# 5_Way_Flex_Switch.net
KiCad netlist of a schematic drawn in EAGLE
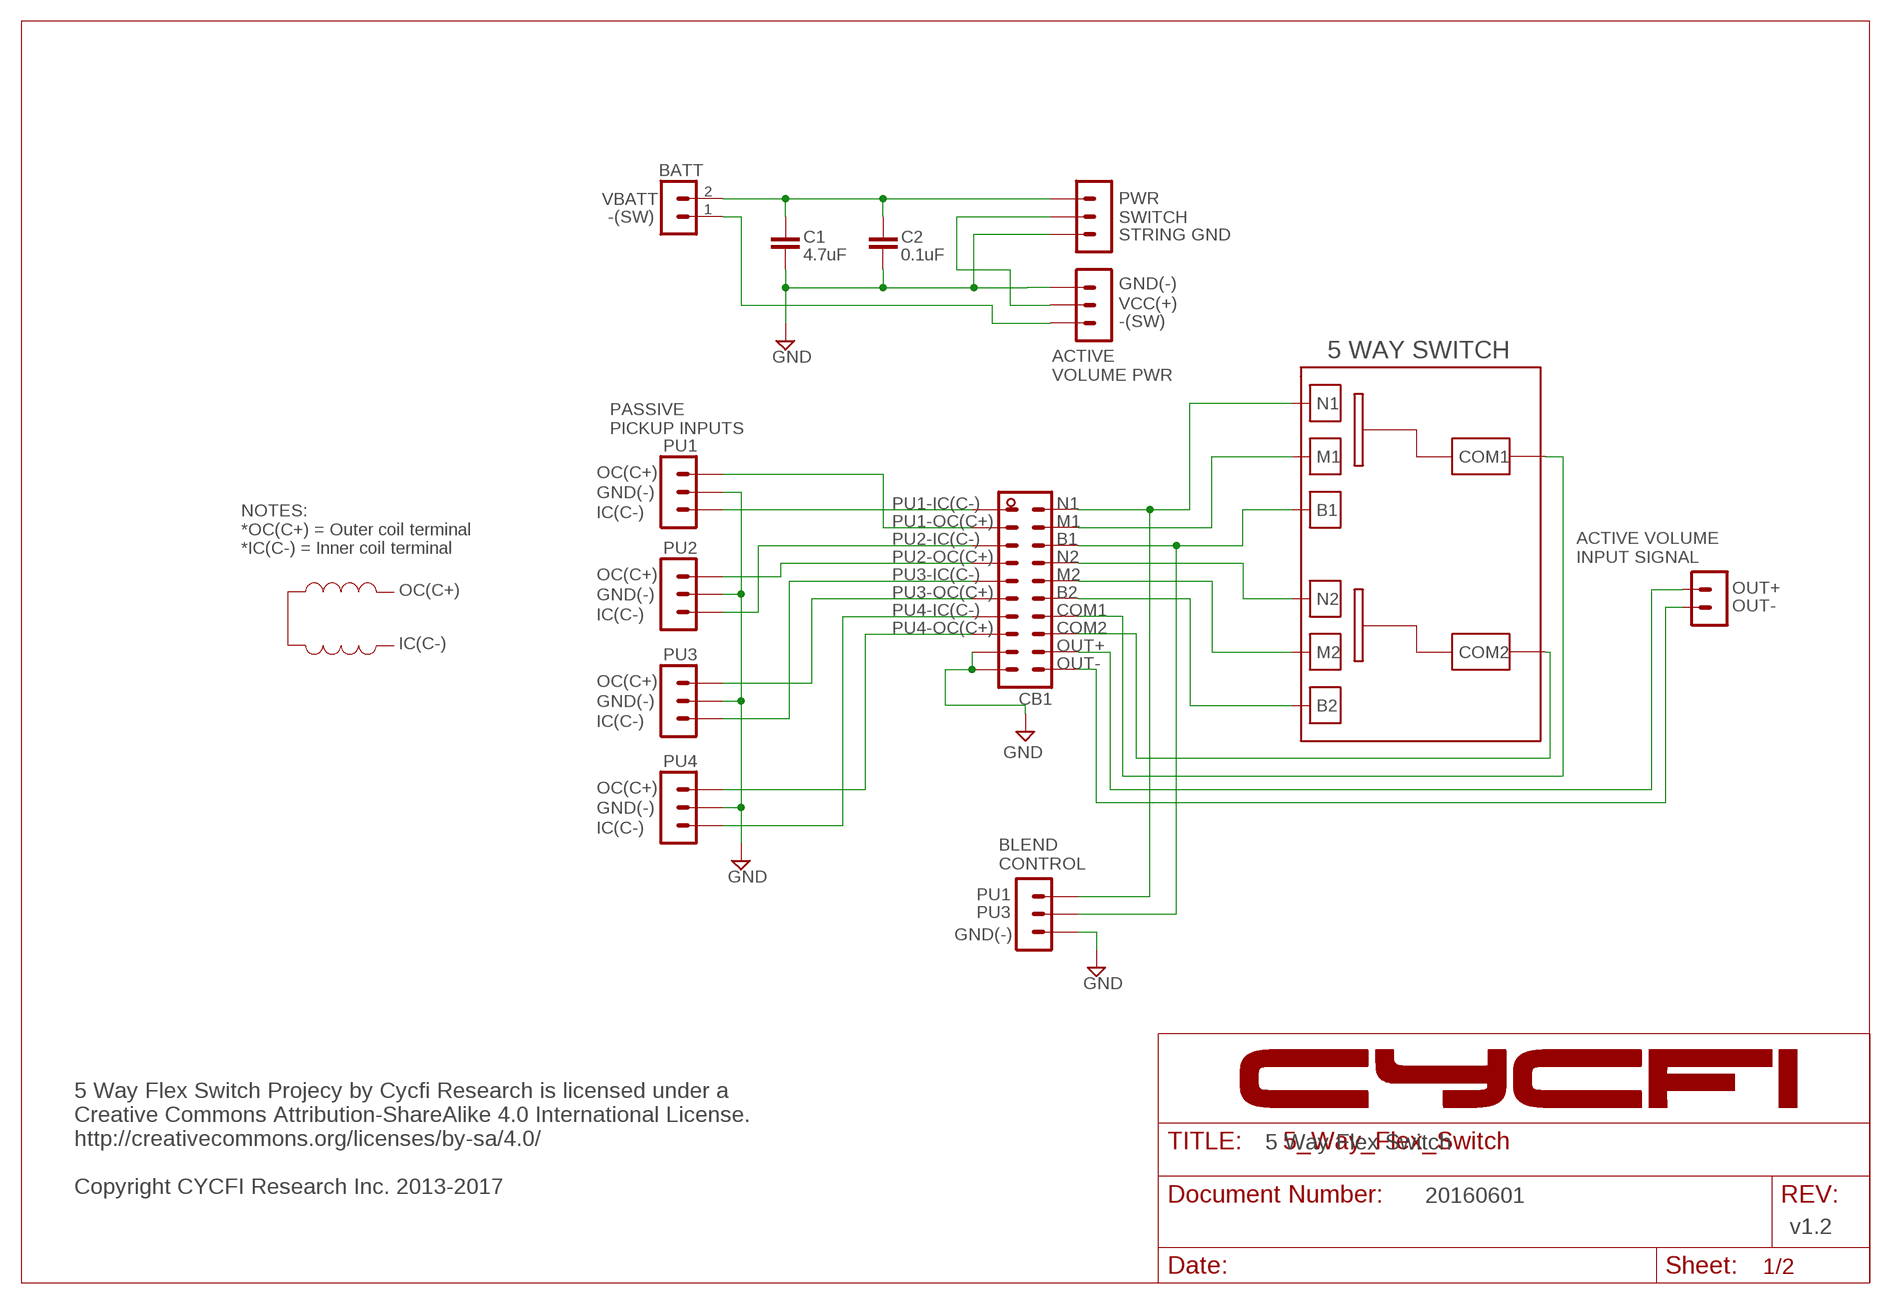
[diagram p0: schematic, sheet 1]
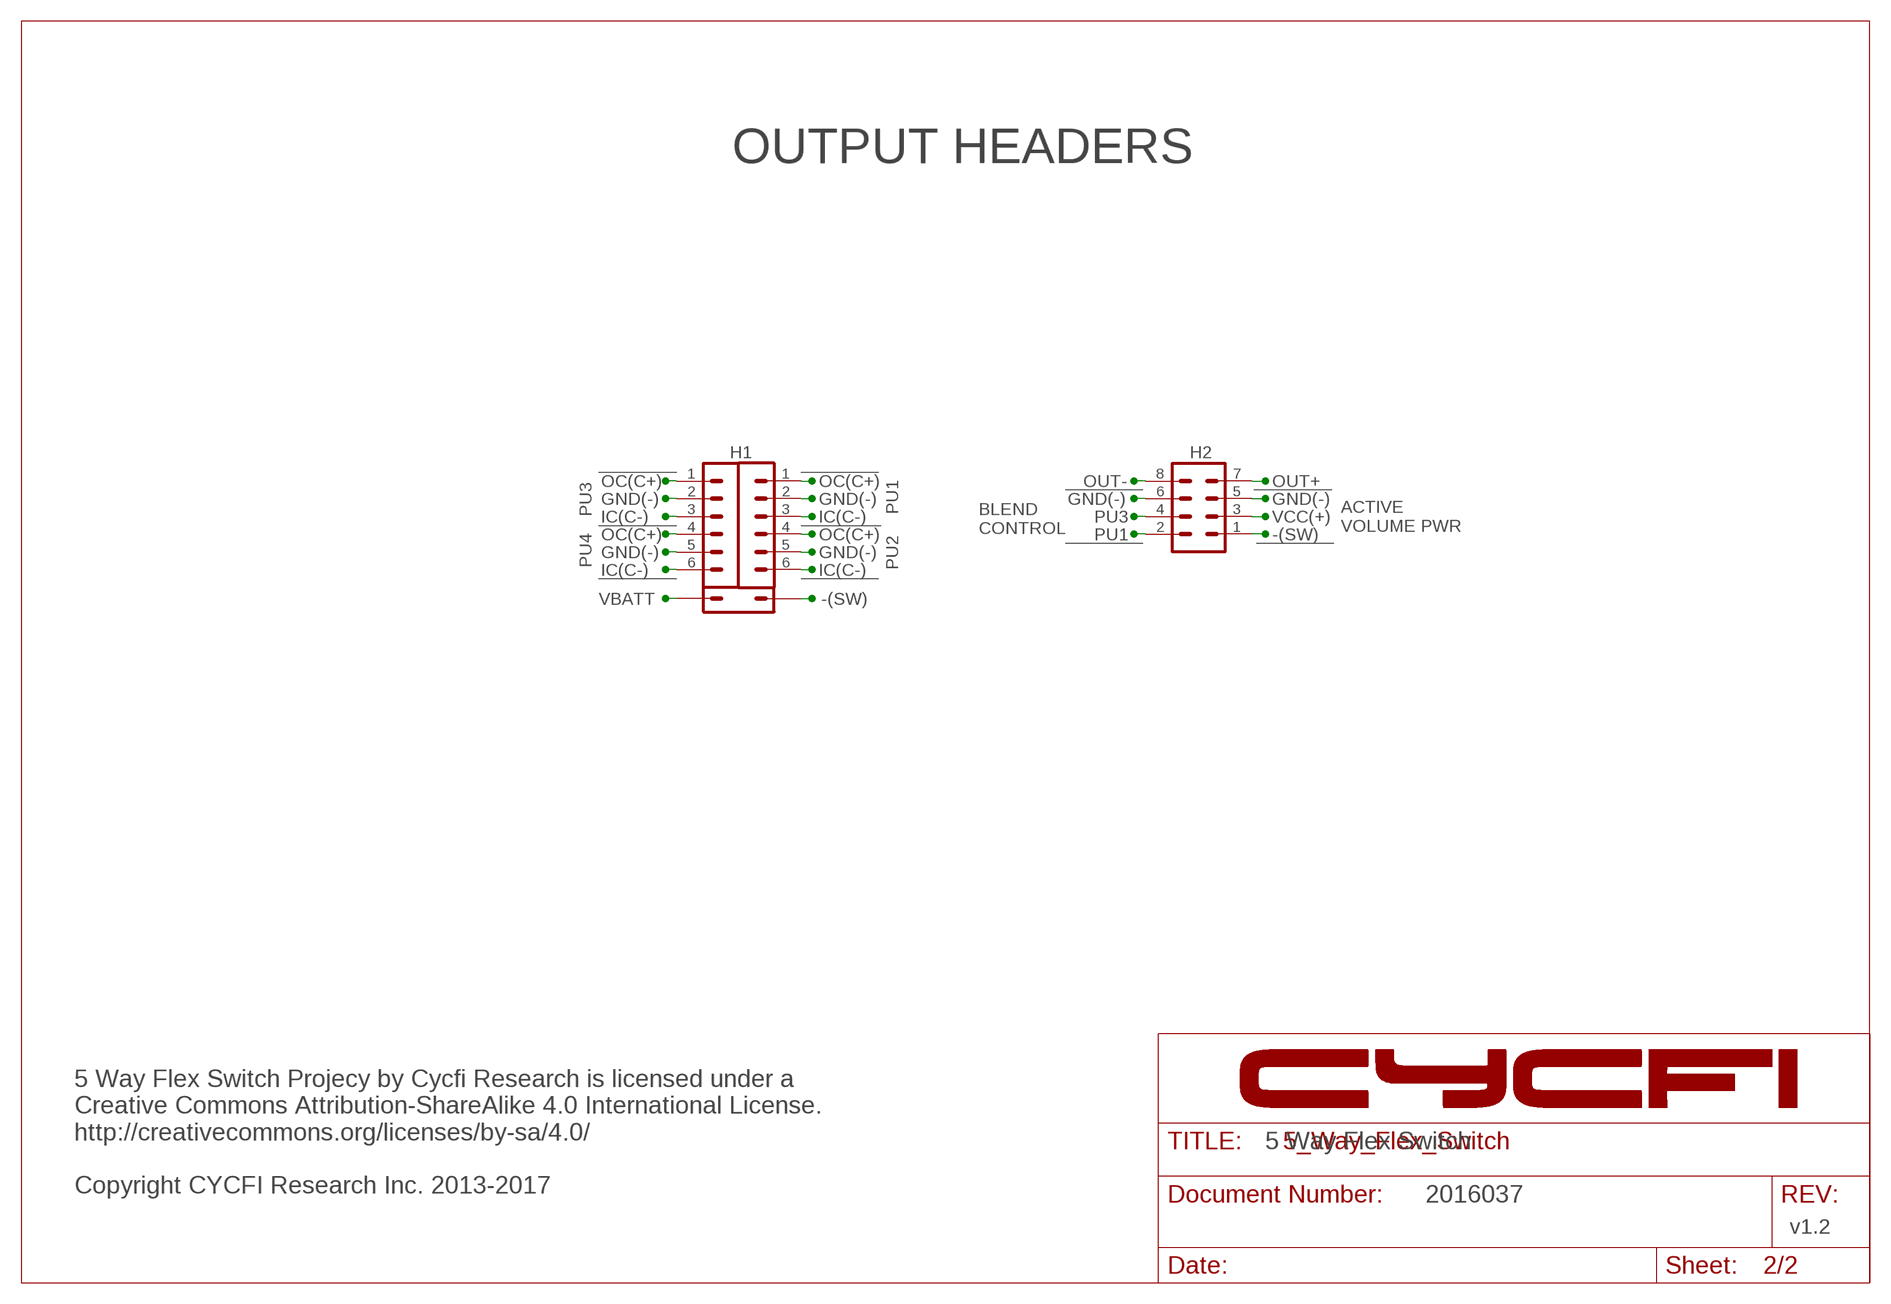
[diagram p1: schematic, sheet 2]

(export (version "E")
  (design (tool "Eeschema 10.0.6"))
  (components
    (comp (ref "H2")
      (value "MA04-2")
      (footprint "eagle-import:MA04-2")
      (libsource (lib "eagle-import") (part "MA04-2"))
    )
    (comp (ref "H4")
      (value "MA06-1EDITED")
      (footprint "eagle-import:MA06-1_")
      (libsource (lib "eagle-import") (part "MA06-1EDITED"))
    )
    (comp (ref "H5")
      (value "MA06-1EDITED")
      (footprint "eagle-import:MA06-1_")
      (libsource (lib "eagle-import") (part "MA06-1EDITED"))
    )
    (comp (ref "C1")
      (value "4.7uF")
      (footprint "eagle-import:C0603")
      (libsource (lib "eagle-import") (part "C-EUC0603"))
    )
    (comp (ref "C2")
      (value "0.1uF")
      (footprint "eagle-import:C0603")
      (libsource (lib "eagle-import") (part "C-EUC0603"))
    )
    (comp (ref "CB1")
      (value "CONFIGURATION_BRD_PADS")
      (footprint "eagle-import:CONFIGURATION_BRD_PADS")
      (libsource (lib "eagle-import") (part "CONFIGURATION_BRD_PADS"))
    )
    (comp (ref "H1")
      (value "MA02-1")
      (footprint "eagle-import:MA02-1")
      (libsource (lib "eagle-import") (part "MA02-1"))
    )
    (comp (ref "H3")
      (value "3PIN-SMD-2.54MM")
      (footprint "eagle-import:3P-SMD-2.54MM")
      (libsource (lib "eagle-import") (part "3PIN-SMD-2.54MM"))
    )
    (comp (ref "U$1")
      (value "5WAY_SW_CASTELLATED")
      (footprint "eagle-import:5WAY_SW_CASTELLATED")
      (libsource (lib "eagle-import") (part "5WAY_SW_CASTELLATED"))
    )
  )
  (nets
    (net (code "1") (name "1-IC") (class "Default")
      (node (ref "CB1") (pin "1-IC") (pinfunction "1-IC_1-IC") (pintype "passive"))
      (node (ref "H4") (pin "3") (pinfunction "3_3") (pintype "passive"))
    )
    (net (code "2") (name "1-OC") (class "Default")
      (node (ref "CB1") (pin "1-OC") (pinfunction "1-OC_1-OC") (pintype "passive"))
      (node (ref "H4") (pin "1") (pinfunction "1_1") (pintype "passive"))
    )
    (net (code "3") (name "2-IC") (class "Default")
      (node (ref "CB1") (pin "2-IC") (pinfunction "2-IC_2-IC") (pintype "passive"))
      (node (ref "H4") (pin "6") (pinfunction "6_6") (pintype "passive"))
    )
    (net (code "4") (name "2-OC") (class "Default")
      (node (ref "CB1") (pin "2-OC") (pinfunction "2-OC_2-OC") (pintype "passive"))
      (node (ref "H4") (pin "4") (pinfunction "4_4") (pintype "passive"))
    )
    (net (code "5") (name "3-IC") (class "Default")
      (node (ref "CB1") (pin "3-IC") (pinfunction "3-IC_3-IC") (pintype "passive"))
      (node (ref "H5") (pin "3") (pinfunction "3_3") (pintype "passive"))
    )
    (net (code "6") (name "3-OC") (class "Default")
      (node (ref "CB1") (pin "3-OC") (pinfunction "3-OC_3-OC") (pintype "passive"))
      (node (ref "H5") (pin "1") (pinfunction "1_1") (pintype "passive"))
    )
    (net (code "7") (name "4-IC") (class "Default")
      (node (ref "CB1") (pin "4-IC") (pinfunction "4-IC_4-IC") (pintype "passive"))
      (node (ref "H5") (pin "6") (pinfunction "6_6") (pintype "passive"))
    )
    (net (code "8") (name "4-OC") (class "Default")
      (node (ref "CB1") (pin "4-OC") (pinfunction "4-OC_4-OC") (pintype "passive"))
      (node (ref "H5") (pin "4") (pinfunction "4_4") (pintype "passive"))
    )
    (net (code "9") (name "B1") (class "Default")
      (node (ref "CB1") (pin "B1") (pinfunction "B1_B1") (pintype "passive"))
      (node (ref "H2") (pin "4") (pinfunction "4_4") (pintype "passive"))
      (node (ref "U$1") (pin "B1") (pinfunction "B1_B1") (pintype "bidirectional"))
    )
    (net (code "10") (name "GND") (class "Default")
      (node (ref "C1") (pin "2") (pinfunction "2_2") (pintype "passive"))
      (node (ref "C2") (pin "2") (pinfunction "2_2") (pintype "passive"))
      (node (ref "CB1") (pin "GND") (pinfunction "GND_GND") (pintype "passive"))
      (node (ref "CB1") (pin "GND1") (pinfunction "GND1_GND1") (pintype "passive"))
      (node (ref "H2") (pin "5") (pinfunction "5_5") (pintype "passive"))
      (node (ref "H2") (pin "6") (pinfunction "6_6") (pintype "passive"))
      (node (ref "H3") (pin "P$3") (pinfunction "3_P$3") (pintype "passive"))
      (node (ref "H4") (pin "2") (pinfunction "2_2") (pintype "passive"))
      (node (ref "H4") (pin "5") (pinfunction "5_5") (pintype "passive"))
      (node (ref "H5") (pin "2") (pinfunction "2_2") (pintype "passive"))
      (node (ref "H5") (pin "5") (pinfunction "5_5") (pintype "passive"))
    )
    (net (code "11") (name "IN+") (class "Default")
      (node (ref "CB1") (pin "OUT-") (pinfunction "OUT-_OUT-") (pintype "passive"))
      (node (ref "H2") (pin "7") (pinfunction "7_7") (pintype "passive"))
    )
    (net (code "12") (name "IN-") (class "Default")
      (node (ref "CB1") (pin "OUT+") (pinfunction "OUT+_OUT+") (pintype "passive"))
      (node (ref "H2") (pin "8") (pinfunction "8_8") (pintype "passive"))
    )
    (net (code "13") (name "N1") (class "Default")
      (node (ref "CB1") (pin "N1") (pinfunction "N1_N1") (pintype "passive"))
      (node (ref "H2") (pin "2") (pinfunction "2_2") (pintype "passive"))
      (node (ref "U$1") (pin "N1") (pinfunction "N1_N1") (pintype "bidirectional"))
    )
    (net (code "14") (name "Net-(CB1-PadB2)") (class "Default")
      (node (ref "CB1") (pin "B2") (pinfunction "B2_B2") (pintype "passive"))
      (node (ref "U$1") (pin "B2") (pinfunction "B2_B2") (pintype "bidirectional"))
    )
    (net (code "15") (name "Net-(CB1-PadCOM1)") (class "Default")
      (node (ref "CB1") (pin "COM1") (pinfunction "COM1_COM1") (pintype "passive"))
      (node (ref "U$1") (pin "COM1") (pinfunction "COM1_COM1") (pintype "bidirectional"))
    )
    (net (code "16") (name "Net-(CB1-PadCOM2)") (class "Default")
      (node (ref "CB1") (pin "COM2") (pinfunction "COM2_COM2") (pintype "passive"))
      (node (ref "U$1") (pin "COM2") (pinfunction "COM2_COM2") (pintype "bidirectional"))
    )
    (net (code "17") (name "Net-(CB1-PadM1)") (class "Default")
      (node (ref "CB1") (pin "M1") (pinfunction "M1_M1") (pintype "passive"))
      (node (ref "U$1") (pin "M1") (pinfunction "M1_M1") (pintype "bidirectional"))
    )
    (net (code "18") (name "Net-(CB1-PadM2)") (class "Default")
      (node (ref "CB1") (pin "M2") (pinfunction "M2_M2") (pintype "passive"))
      (node (ref "U$1") (pin "M2") (pinfunction "M2_M2") (pintype "bidirectional"))
    )
    (net (code "19") (name "Net-(CB1-PadN2)") (class "Default")
      (node (ref "CB1") (pin "N2") (pinfunction "N2_N2") (pintype "passive"))
      (node (ref "U$1") (pin "N2") (pinfunction "N2_N2") (pintype "bidirectional"))
    )
    (net (code "20") (name "SW") (class "Default")
      (node (ref "H1") (pin "1") (pinfunction "1_1") (pintype "passive"))
      (node (ref "H2") (pin "1") (pinfunction "1_1") (pintype "passive"))
    )
    (net (code "21") (name "VBATT") (class "Default")
      (node (ref "C1") (pin "1") (pinfunction "1_1") (pintype "passive"))
      (node (ref "C2") (pin "1") (pinfunction "1_1") (pintype "passive"))
      (node (ref "H1") (pin "2") (pinfunction "2_2") (pintype "passive"))
      (node (ref "H3") (pin "P$1") (pinfunction "1_P$1") (pintype "passive"))
    )
    (net (code "22") (name "VCC") (class "Default")
      (node (ref "H2") (pin "3") (pinfunction "3_3") (pintype "passive"))
      (node (ref "H3") (pin "P$2") (pinfunction "2_P$2") (pintype "passive"))
    )
  )
)
